# traffic_light.net
KiCad netlist of a schematic drawn in EAGLE
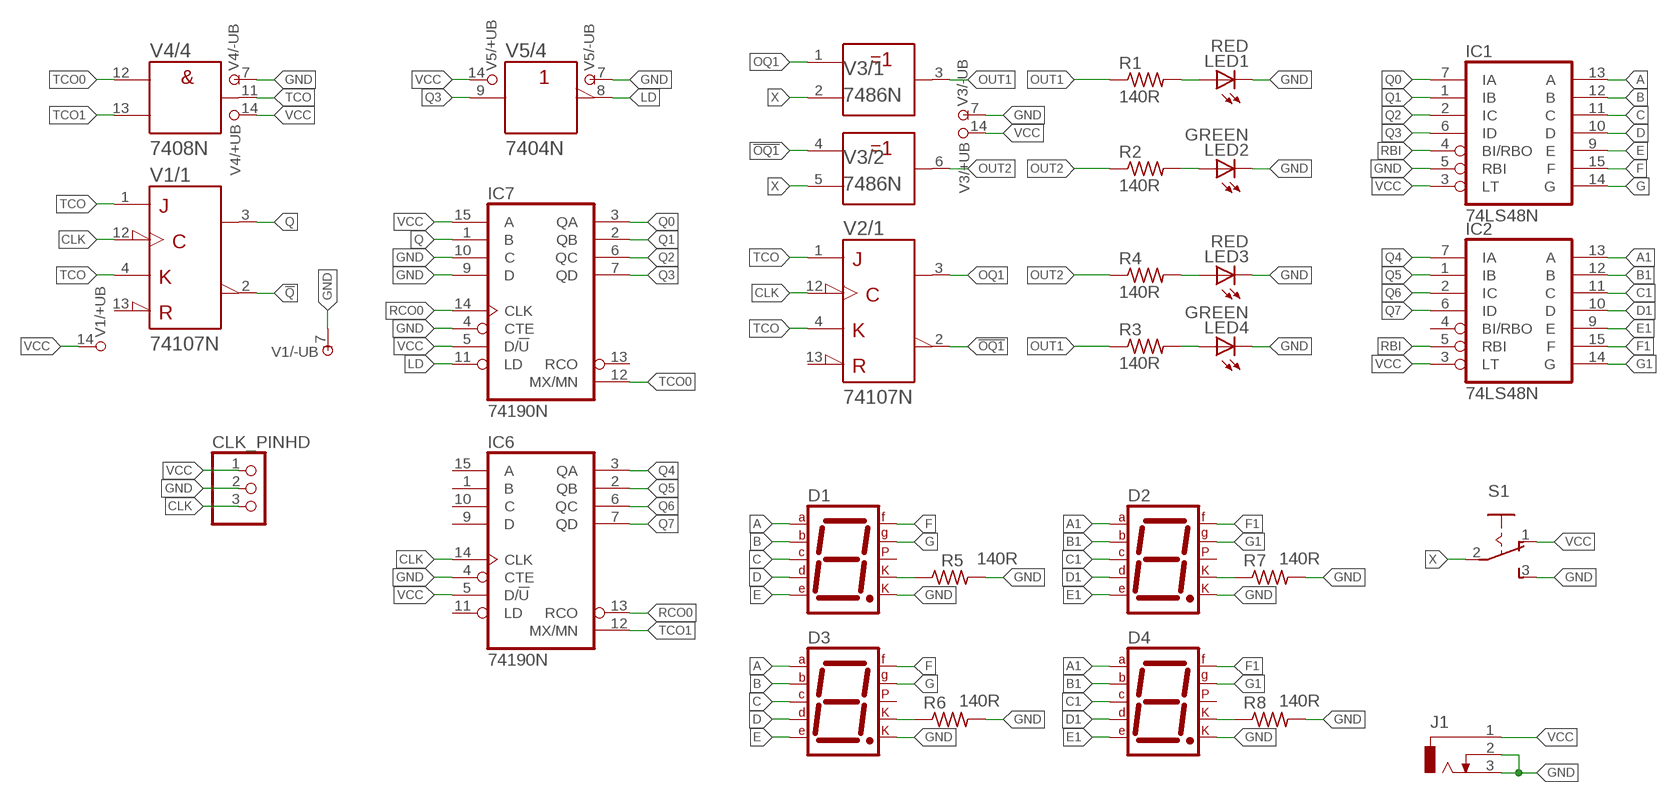
[diagram p0: schematic, sheet 1]

(export (version "E")
  (design (tool "Eeschema 10.0.6"))
  (components
    (comp (ref "CLK_PINHD")
      (value "PINHD-1X3")
      (footprint "eagle-import:1X03")
      (libsource (lib "eagle-import") (part "PINHD-1X3"))
    )
    (comp (ref "D1")
      (value "7SEG-CK")
      (footprint "eagle-import:7SEG-13")
      (libsource (lib "eagle-import") (part "7SEG-CK"))
    )
    (comp (ref "D2")
      (value "7SEG-CK")
      (footprint "eagle-import:7SEG-13")
      (libsource (lib "eagle-import") (part "7SEG-CK"))
    )
    (comp (ref "D3")
      (value "7SEG-CK")
      (footprint "eagle-import:7SEG-13")
      (libsource (lib "eagle-import") (part "7SEG-CK"))
    )
    (comp (ref "D4")
      (value "7SEG-CK")
      (footprint "eagle-import:7SEG-13")
      (libsource (lib "eagle-import") (part "7SEG-CK"))
    )
    (comp (ref "IC1")
      (value "74LS48N")
      (footprint "eagle-import:DIL16")
      (libsource (lib "eagle-import") (part "7448NLS"))
    )
    (comp (ref "IC2")
      (value "74LS48N")
      (footprint "eagle-import:DIL16")
      (libsource (lib "eagle-import") (part "7448NLS"))
    )
    (comp (ref "IC6")
      (value "74190N")
      (footprint "eagle-import:DIL16")
      (libsource (lib "eagle-import") (part "74190N"))
    )
    (comp (ref "IC7")
      (value "74190N")
      (footprint "eagle-import:DIL16")
      (libsource (lib "eagle-import") (part "74190N"))
    )
    (comp (ref "J1")
      (value "CON_JACK")
      (footprint "eagle-import:DCJ0303")
      (libsource (lib "eagle-import") (part "CON_JACK"))
    )
    (comp (ref "LED1")
      (value "RED")
      (footprint "eagle-import:LED5MM")
      (libsource (lib "eagle-import") (part "LED5MM"))
    )
    (comp (ref "LED2")
      (value "GREEN")
      (footprint "eagle-import:LED5MM")
      (libsource (lib "eagle-import") (part "LED5MM"))
    )
    (comp (ref "LED3")
      (value "RED")
      (footprint "eagle-import:LED5MM")
      (libsource (lib "eagle-import") (part "LED5MM"))
    )
    (comp (ref "LED4")
      (value "GREEN")
      (footprint "eagle-import:LED5MM")
      (libsource (lib "eagle-import") (part "LED5MM"))
    )
    (comp (ref "R1")
      (value "140R")
      (footprint "eagle-import:0204_7")
      (libsource (lib "eagle-import") (part "RES-7"))
    )
    (comp (ref "R2")
      (value "140R")
      (footprint "eagle-import:0204_7")
      (libsource (lib "eagle-import") (part "RES-7"))
    )
    (comp (ref "R3")
      (value "140R")
      (footprint "eagle-import:0204_7")
      (libsource (lib "eagle-import") (part "RES-7"))
    )
    (comp (ref "R4")
      (value "140R")
      (footprint "eagle-import:0204_7")
      (libsource (lib "eagle-import") (part "RES-7"))
    )
    (comp (ref "R5")
      (value "140R")
      (footprint "eagle-import:0204_7")
      (libsource (lib "eagle-import") (part "RES-7"))
    )
    (comp (ref "R6")
      (value "140R")
      (footprint "eagle-import:0204_7")
      (libsource (lib "eagle-import") (part "RES-7"))
    )
    (comp (ref "R7")
      (value "140R")
      (footprint "eagle-import:0204_7")
      (libsource (lib "eagle-import") (part "RES-7"))
    )
    (comp (ref "R8")
      (value "140R")
      (footprint "eagle-import:0204_7")
      (libsource (lib "eagle-import") (part "RES-7"))
    )
    (comp (ref "S1")
      (value "255SB")
      (footprint "eagle-import:255SB")
      (libsource (lib "eagle-import") (part "255SB"))
    )
    (comp (ref "V1")
      (value "74107N")
      (footprint "eagle-import:DIL14")
      (libsource (lib "eagle-import") (part "74107N"))
    )
    (comp (ref "V2")
      (value "74107N")
      (footprint "eagle-import:DIL14")
      (libsource (lib "eagle-import") (part "74107N"))
    )
    (comp (ref "V3")
      (value "7486N")
      (footprint "eagle-import:DIL14")
      (libsource (lib "eagle-import") (part "7486N"))
    )
    (comp (ref "V4")
      (value "7408N")
      (footprint "eagle-import:DIL14")
      (libsource (lib "eagle-import") (part "7408N"))
    )
    (comp (ref "V5")
      (value "7404N")
      (footprint "eagle-import:DIL14")
      (libsource (lib "eagle-import") (part "7404N"))
    )
  )
  (nets
    (net (code "1") (name "/~{OQ1}") (class "Default")
      (node (ref "V2") (pin "2") (pinfunction "~{Q}_2") (pintype "output"))
      (node (ref "V3") (pin "4") (pinfunction "A_4") (pintype "input"))
    )
    (net (code "2") (name "/~{Q}") (class "Default")
      (node (ref "V1") (pin "2") (pinfunction "~{Q}_2") (pintype "output"))
    )
    (net (code "3") (name "A") (class "Default")
      (node (ref "D1") (pin "7") (pinfunction "A_7") (pintype "passive"))
      (node (ref "D3") (pin "7") (pinfunction "A_7") (pintype "passive"))
      (node (ref "IC1") (pin "13") (pinfunction "A_13") (pintype "output"))
    )
    (net (code "4") (name "A1") (class "Default")
      (node (ref "D2") (pin "7") (pinfunction "A_7") (pintype "passive"))
      (node (ref "D4") (pin "7") (pinfunction "A_7") (pintype "passive"))
      (node (ref "IC2") (pin "13") (pinfunction "A_13") (pintype "output"))
    )
    (net (code "5") (name "B") (class "Default")
      (node (ref "D1") (pin "6") (pinfunction "B_6") (pintype "passive"))
      (node (ref "D3") (pin "6") (pinfunction "B_6") (pintype "passive"))
      (node (ref "IC1") (pin "12") (pinfunction "B_12") (pintype "output"))
    )
    (net (code "6") (name "B1") (class "Default")
      (node (ref "D2") (pin "6") (pinfunction "B_6") (pintype "passive"))
      (node (ref "D4") (pin "6") (pinfunction "B_6") (pintype "passive"))
      (node (ref "IC2") (pin "12") (pinfunction "B_12") (pintype "output"))
    )
    (net (code "7") (name "C") (class "Default")
      (node (ref "D1") (pin "4") (pinfunction "C_4") (pintype "passive"))
      (node (ref "D3") (pin "4") (pinfunction "C_4") (pintype "passive"))
      (node (ref "IC1") (pin "11") (pinfunction "C_11") (pintype "output"))
    )
    (net (code "8") (name "C1") (class "Default")
      (node (ref "D2") (pin "4") (pinfunction "C_4") (pintype "passive"))
      (node (ref "D4") (pin "4") (pinfunction "C_4") (pintype "passive"))
      (node (ref "IC2") (pin "11") (pinfunction "C_11") (pintype "output"))
    )
    (net (code "9") (name "CLK") (class "Default")
      (node (ref "CLK_PINHD") (pin "3") (pinfunction "3_3") (pintype "passive"))
      (node (ref "IC6") (pin "14") (pinfunction "CLK_14") (pintype "input"))
      (node (ref "V1") (pin "12") (pinfunction "CLK_12") (pintype "input"))
      (node (ref "V2") (pin "12") (pinfunction "CLK_12") (pintype "input"))
    )
    (net (code "10") (name "D") (class "Default")
      (node (ref "D1") (pin "2") (pinfunction "D_2") (pintype "passive"))
      (node (ref "D3") (pin "2") (pinfunction "D_2") (pintype "passive"))
      (node (ref "IC1") (pin "10") (pinfunction "D_10") (pintype "output"))
    )
    (net (code "11") (name "D1") (class "Default")
      (node (ref "D2") (pin "2") (pinfunction "D_2") (pintype "passive"))
      (node (ref "D4") (pin "2") (pinfunction "D_2") (pintype "passive"))
      (node (ref "IC2") (pin "10") (pinfunction "D_10") (pintype "output"))
    )
    (net (code "12") (name "E") (class "Default")
      (node (ref "D1") (pin "1") (pinfunction "E_1") (pintype "passive"))
      (node (ref "D3") (pin "1") (pinfunction "E_1") (pintype "passive"))
      (node (ref "IC1") (pin "9") (pinfunction "E_9") (pintype "output"))
    )
    (net (code "13") (name "E1") (class "Default")
      (node (ref "D2") (pin "1") (pinfunction "E_1") (pintype "passive"))
      (node (ref "D4") (pin "1") (pinfunction "E_1") (pintype "passive"))
      (node (ref "IC2") (pin "9") (pinfunction "E_9") (pintype "output"))
    )
    (net (code "14") (name "F") (class "Default")
      (node (ref "D1") (pin "9") (pinfunction "F_9") (pintype "passive"))
      (node (ref "D3") (pin "9") (pinfunction "F_9") (pintype "passive"))
      (node (ref "IC1") (pin "15") (pinfunction "F_15") (pintype "output"))
    )
    (net (code "15") (name "F1") (class "Default")
      (node (ref "D2") (pin "9") (pinfunction "F_9") (pintype "passive"))
      (node (ref "D4") (pin "9") (pinfunction "F_9") (pintype "passive"))
      (node (ref "IC2") (pin "15") (pinfunction "F_15") (pintype "output"))
    )
    (net (code "16") (name "G") (class "Default")
      (node (ref "D1") (pin "10") (pinfunction "G_10") (pintype "passive"))
      (node (ref "D3") (pin "10") (pinfunction "G_10") (pintype "passive"))
      (node (ref "IC1") (pin "14") (pinfunction "G_14") (pintype "output"))
    )
    (net (code "17") (name "G1") (class "Default")
      (node (ref "D2") (pin "10") (pinfunction "G_10") (pintype "passive"))
      (node (ref "D4") (pin "10") (pinfunction "G_10") (pintype "passive"))
      (node (ref "IC2") (pin "14") (pinfunction "G_14") (pintype "output"))
    )
    (net (code "18") (name "GND") (class "Default")
      (node (ref "CLK_PINHD") (pin "2") (pinfunction "2_2") (pintype "passive"))
      (node (ref "D1") (pin "8") (pinfunction "CK2_8") (pintype "passive"))
      (node (ref "D2") (pin "8") (pinfunction "CK2_8") (pintype "passive"))
      (node (ref "D3") (pin "8") (pinfunction "CK2_8") (pintype "passive"))
      (node (ref "D4") (pin "8") (pinfunction "CK2_8") (pintype "passive"))
      (node (ref "IC1") (pin "5") (pinfunction "RBI_5") (pintype "input"))
      (node (ref "IC6") (pin "4") (pinfunction "CTE_4") (pintype "input"))
      (node (ref "IC7") (pin "10") (pinfunction "C_10") (pintype "input"))
      (node (ref "IC7") (pin "4") (pinfunction "CTE_4") (pintype "input"))
      (node (ref "IC7") (pin "9") (pinfunction "D_9") (pintype "input"))
      (node (ref "J1") (pin "2") (pinfunction "2_2") (pintype "passive"))
      (node (ref "J1") (pin "3") (pinfunction "3_3") (pintype "passive"))
      (node (ref "LED1") (pin "K") (pinfunction "C_K") (pintype "passive"))
      (node (ref "LED2") (pin "K") (pinfunction "C_K") (pintype "passive"))
      (node (ref "LED3") (pin "K") (pinfunction "C_K") (pintype "passive"))
      (node (ref "LED4") (pin "K") (pinfunction "C_K") (pintype "passive"))
      (node (ref "R5") (pin "2") (pinfunction "2_2") (pintype "passive"))
      (node (ref "R6") (pin "2") (pinfunction "2_2") (pintype "passive"))
      (node (ref "R7") (pin "2") (pinfunction "2_2") (pintype "passive"))
      (node (ref "R8") (pin "2") (pinfunction "2_2") (pintype "passive"))
      (node (ref "S1") (pin "3") (pinfunction "S_3") (pintype "passive"))
      (node (ref "V1") (pin "7") (pinfunction "-UB_7") (pintype "power_in"))
      (node (ref "V3") (pin "7") (pinfunction "-UB_7") (pintype "power_in"))
      (node (ref "V4") (pin "7") (pinfunction "-UB_7") (pintype "power_in"))
      (node (ref "V5") (pin "7") (pinfunction "-UB_7") (pintype "power_in"))
    )
    (net (code "19") (name "LD") (class "Default")
      (node (ref "IC7") (pin "11") (pinfunction "LD_11") (pintype "input"))
      (node (ref "V5") (pin "8") (pinfunction "Y_8") (pintype "output"))
    )
    (net (code "20") (name "Net-(D1-CK1)") (class "Default")
      (node (ref "D1") (pin "3") (pinfunction "CK1_3") (pintype "passive"))
      (node (ref "R5") (pin "1") (pinfunction "1_1") (pintype "passive"))
    )
    (net (code "21") (name "Net-(D2-CK1)") (class "Default")
      (node (ref "D2") (pin "3") (pinfunction "CK1_3") (pintype "passive"))
      (node (ref "R7") (pin "1") (pinfunction "1_1") (pintype "passive"))
    )
    (net (code "22") (name "Net-(D3-CK1)") (class "Default")
      (node (ref "D3") (pin "3") (pinfunction "CK1_3") (pintype "passive"))
      (node (ref "R6") (pin "1") (pinfunction "1_1") (pintype "passive"))
    )
    (net (code "23") (name "Net-(D4-CK1)") (class "Default")
      (node (ref "D4") (pin "3") (pinfunction "CK1_3") (pintype "passive"))
      (node (ref "R8") (pin "1") (pinfunction "1_1") (pintype "passive"))
    )
    (net (code "24") (name "Net-(LED1-PadA)") (class "Default")
      (node (ref "LED1") (pin "A") (pinfunction "A_A") (pintype "passive"))
      (node (ref "R1") (pin "2") (pinfunction "2_2") (pintype "passive"))
    )
    (net (code "25") (name "Net-(LED2-PadA)") (class "Default")
      (node (ref "LED2") (pin "A") (pinfunction "A_A") (pintype "passive"))
      (node (ref "R2") (pin "2") (pinfunction "2_2") (pintype "passive"))
    )
    (net (code "26") (name "Net-(LED3-PadA)") (class "Default")
      (node (ref "LED3") (pin "A") (pinfunction "A_A") (pintype "passive"))
      (node (ref "R4") (pin "2") (pinfunction "2_2") (pintype "passive"))
    )
    (net (code "27") (name "Net-(LED4-PadA)") (class "Default")
      (node (ref "LED4") (pin "A") (pinfunction "A_A") (pintype "passive"))
      (node (ref "R3") (pin "2") (pinfunction "2_2") (pintype "passive"))
    )
    (net (code "28") (name "OQ1") (class "Default")
      (node (ref "V2") (pin "3") (pinfunction "Q_3") (pintype "output"))
      (node (ref "V3") (pin "1") (pinfunction "A_1") (pintype "input"))
    )
    (net (code "29") (name "OUT1") (class "Default")
      (node (ref "R1") (pin "1") (pinfunction "1_1") (pintype "passive"))
      (node (ref "R3") (pin "1") (pinfunction "1_1") (pintype "passive"))
      (node (ref "V3") (pin "3") (pinfunction "Y_3") (pintype "output"))
    )
    (net (code "30") (name "OUT2") (class "Default")
      (node (ref "R2") (pin "1") (pinfunction "1_1") (pintype "passive"))
      (node (ref "R4") (pin "1") (pinfunction "1_1") (pintype "passive"))
      (node (ref "V3") (pin "6") (pinfunction "Y_6") (pintype "output"))
    )
    (net (code "31") (name "Q") (class "Default")
      (node (ref "IC7") (pin "1") (pinfunction "B_1") (pintype "input"))
      (node (ref "V1") (pin "3") (pinfunction "Q_3") (pintype "output"))
    )
    (net (code "32") (name "Q0") (class "Default")
      (node (ref "IC1") (pin "7") (pinfunction "IA_7") (pintype "input"))
      (node (ref "IC7") (pin "3") (pinfunction "QA_3") (pintype "output"))
    )
    (net (code "33") (name "Q1") (class "Default")
      (node (ref "IC1") (pin "1") (pinfunction "IB_1") (pintype "input"))
      (node (ref "IC7") (pin "2") (pinfunction "QB_2") (pintype "output"))
    )
    (net (code "34") (name "Q2") (class "Default")
      (node (ref "IC1") (pin "2") (pinfunction "IC_2") (pintype "input"))
      (node (ref "IC7") (pin "6") (pinfunction "QC_6") (pintype "output"))
    )
    (net (code "35") (name "Q3") (class "Default")
      (node (ref "IC1") (pin "6") (pinfunction "ID_6") (pintype "input"))
      (node (ref "IC7") (pin "7") (pinfunction "QD_7") (pintype "output"))
      (node (ref "V5") (pin "9") (pinfunction "A_9") (pintype "input"))
    )
    (net (code "36") (name "Q4") (class "Default")
      (node (ref "IC2") (pin "7") (pinfunction "IA_7") (pintype "input"))
      (node (ref "IC6") (pin "3") (pinfunction "QA_3") (pintype "output"))
    )
    (net (code "37") (name "Q5") (class "Default")
      (node (ref "IC2") (pin "1") (pinfunction "IB_1") (pintype "input"))
      (node (ref "IC6") (pin "2") (pinfunction "QB_2") (pintype "output"))
    )
    (net (code "38") (name "Q6") (class "Default")
      (node (ref "IC2") (pin "2") (pinfunction "IC_2") (pintype "input"))
      (node (ref "IC6") (pin "6") (pinfunction "QC_6") (pintype "output"))
    )
    (net (code "39") (name "Q7") (class "Default")
      (node (ref "IC2") (pin "6") (pinfunction "ID_6") (pintype "input"))
      (node (ref "IC6") (pin "7") (pinfunction "QD_7") (pintype "output"))
    )
    (net (code "40") (name "RBI") (class "Default")
      (node (ref "IC1") (pin "4") (pinfunction "BI/RBO_4") (pintype "input"))
      (node (ref "IC2") (pin "5") (pinfunction "RBI_5") (pintype "input"))
    )
    (net (code "41") (name "RCO0") (class "Default")
      (node (ref "IC6") (pin "13") (pinfunction "RCO_13") (pintype "output"))
      (node (ref "IC7") (pin "14") (pinfunction "CLK_14") (pintype "input"))
    )
    (net (code "42") (name "TCO") (class "Default")
      (node (ref "V1") (pin "1") (pinfunction "J_1") (pintype "input"))
      (node (ref "V1") (pin "4") (pinfunction "K_4") (pintype "input"))
      (node (ref "V2") (pin "1") (pinfunction "J_1") (pintype "input"))
      (node (ref "V2") (pin "4") (pinfunction "K_4") (pintype "input"))
      (node (ref "V4") (pin "11") (pinfunction "Y_11") (pintype "output"))
    )
    (net (code "43") (name "TCO0") (class "Default")
      (node (ref "IC7") (pin "12") (pinfunction "MX/MN_12") (pintype "output"))
      (node (ref "V4") (pin "12") (pinfunction "A_12") (pintype "input"))
    )
    (net (code "44") (name "TCO1") (class "Default")
      (node (ref "IC6") (pin "12") (pinfunction "MX/MN_12") (pintype "output"))
      (node (ref "V4") (pin "13") (pinfunction "B_13") (pintype "input"))
    )
    (net (code "45") (name "VCC") (class "Default")
      (node (ref "CLK_PINHD") (pin "1") (pinfunction "1_1") (pintype "passive"))
      (node (ref "IC1") (pin "3") (pinfunction "LT_3") (pintype "input"))
      (node (ref "IC2") (pin "3") (pinfunction "LT_3") (pintype "input"))
      (node (ref "IC6") (pin "5") (pinfunction "D/~{U}_5") (pintype "input"))
      (node (ref "IC7") (pin "15") (pinfunction "A_15") (pintype "input"))
      (node (ref "IC7") (pin "5") (pinfunction "D/~{U}_5") (pintype "input"))
      (node (ref "J1") (pin "1") (pinfunction "1_1") (pintype "passive"))
      (node (ref "S1") (pin "1") (pinfunction "O_1") (pintype "passive"))
      (node (ref "V1") (pin "14") (pinfunction "+UB_14") (pintype "power_in"))
      (node (ref "V3") (pin "14") (pinfunction "+UB_14") (pintype "power_in"))
      (node (ref "V4") (pin "14") (pinfunction "+UB_14") (pintype "power_in"))
      (node (ref "V5") (pin "14") (pinfunction "+UB_14") (pintype "power_in"))
    )
    (net (code "46") (name "X") (class "Default")
      (node (ref "S1") (pin "2") (pinfunction "P_2") (pintype "passive"))
      (node (ref "V3") (pin "2") (pinfunction "B_2") (pintype "input"))
      (node (ref "V3") (pin "5") (pinfunction "B_5") (pintype "input"))
    )
    (net (code "47") (name "unconnected-(D1-DP-Pad5)") (class "Default")
      (node (ref "D1") (pin "5") (pinfunction "DP_5") (pintype "passive"))
    )
    (net (code "48") (name "unconnected-(D2-DP-Pad5)") (class "Default")
      (node (ref "D2") (pin "5") (pinfunction "DP_5") (pintype "passive"))
    )
    (net (code "49") (name "unconnected-(D3-DP-Pad5)") (class "Default")
      (node (ref "D3") (pin "5") (pinfunction "DP_5") (pintype "passive"))
    )
    (net (code "50") (name "unconnected-(D4-DP-Pad5)") (class "Default")
      (node (ref "D4") (pin "5") (pinfunction "DP_5") (pintype "passive"))
    )
    (net (code "51") (name "unconnected-(IC2A-BI{slash}RBO-Pad4)") (class "Default")
      (node (ref "IC2") (pin "4") (pinfunction "BI/RBO_4") (pintype "input"))
    )
    (net (code "52") (name "unconnected-(IC6A-A-Pad15)") (class "Default")
      (node (ref "IC6") (pin "15") (pinfunction "A_15") (pintype "input"))
    )
    (net (code "53") (name "unconnected-(IC6A-B-Pad1)") (class "Default")
      (node (ref "IC6") (pin "1") (pinfunction "B_1") (pintype "input"))
    )
    (net (code "54") (name "unconnected-(IC6A-C-Pad10)") (class "Default")
      (node (ref "IC6") (pin "10") (pinfunction "C_10") (pintype "input"))
    )
    (net (code "55") (name "unconnected-(IC6A-D-Pad9)") (class "Default")
      (node (ref "IC6") (pin "9") (pinfunction "D_9") (pintype "input"))
    )
    (net (code "56") (name "unconnected-(IC6A-LD-Pad11)") (class "Default")
      (node (ref "IC6") (pin "11") (pinfunction "LD_11") (pintype "input"))
    )
    (net (code "57") (name "unconnected-(IC7A-RCO-Pad13)") (class "Default")
      (node (ref "IC7") (pin "13") (pinfunction "RCO_13") (pintype "output"))
    )
    (net (code "58") (name "unconnected-(V1C-~{CLR}-Pad13)") (class "Default")
      (node (ref "V1") (pin "13") (pinfunction "~{CLR}_13") (pintype "input"))
    )
    (net (code "59") (name "unconnected-(V2C-~{CLR}-Pad13)") (class "Default")
      (node (ref "V2") (pin "13") (pinfunction "~{CLR}_13") (pintype "input"))
    )
  )
)
